# RNS.net
KiCad netlist of a schematic drawn in EAGLE
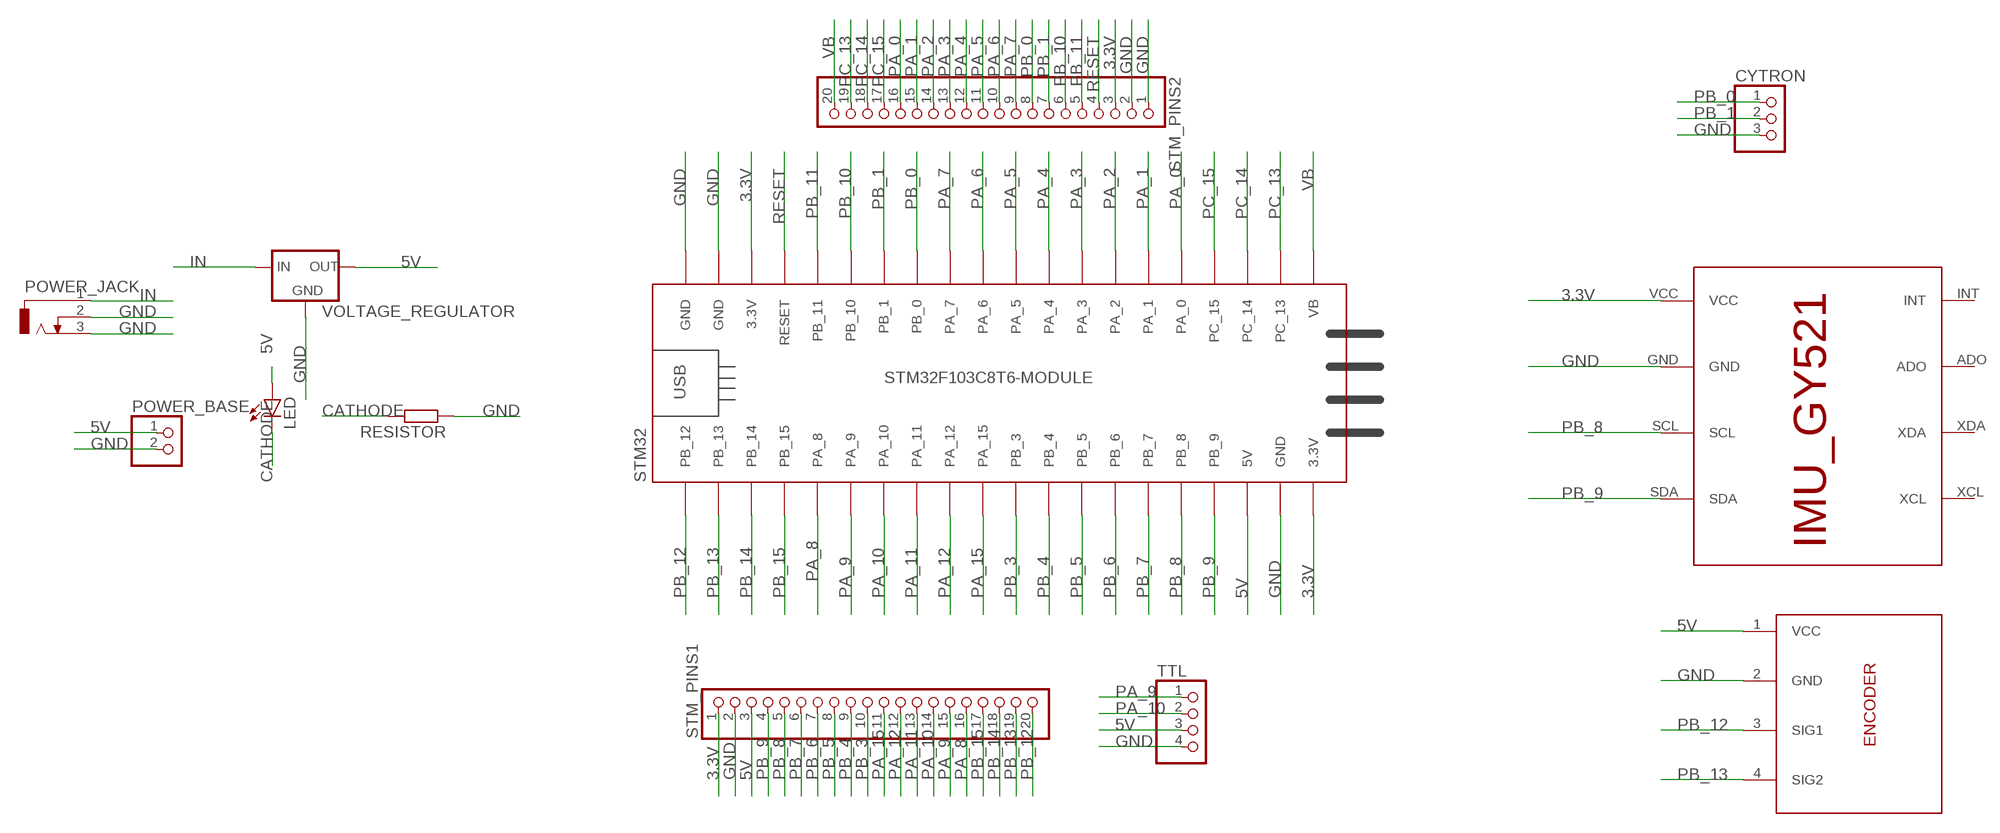
[diagram p0: schematic, sheet 1]

(export (version "E")
  (design (tool "Eeschema 10.0.6"))
  (components
    (comp (ref "CYTRON")
      (value "PINHD-3_DATA")
      (footprint "eagle-import:1X03_DATA")
      (libsource (lib "eagle-import") (part "PINHD-3_DATA"))
    )
    (comp (ref "ENCODER")
      (value "ENCODER")
      (footprint "eagle-import:1X04_DATA")
      (libsource (lib "eagle-import") (part "ENCODER"))
    )
    (comp (ref "IMU")
      (value "IMU_ROBOCON_GY521")
      (footprint "eagle-import:IMU_GY521")
      (libsource (lib "eagle-import") (part "IMU_ROBOCON_GY521"))
    )
    (comp (ref "LED")
      (value "LED5MM")
      (footprint "eagle-import:LED5MM")
      (libsource (lib "eagle-import") (part "LED5MM"))
    )
    (comp (ref "POWER_BASE")
      (value "PINHD-2_DATA")
      (footprint "eagle-import:1X02_DATA")
      (libsource (lib "eagle-import") (part "PINHD-2_DATA"))
    )
    (comp (ref "POWER_JACK")
      (value "CON_JACK")
      (footprint "eagle-import:DCJ0303")
      (libsource (lib "eagle-import") (part "CON_JACK"))
    )
    (comp (ref "RESISTOR")
      (value "R-EU_0207/12")
      (footprint "eagle-import:0207_12")
      (libsource (lib "eagle-import") (part "R-EU_0207/12"))
    )
    (comp (ref "STM32")
      (value "STM32F103C8T6-MODULE")
      (footprint "eagle-import:STM32F103C8T6-MODULE")
      (libsource (lib "eagle-import") (part "STM32F103C8T6-MODULE"))
    )
    (comp (ref "STM_PINS1")
      (value "PINHD-1X20")
      (footprint "eagle-import:1X20")
      (libsource (lib "eagle-import") (part "PINHD-1X20"))
    )
    (comp (ref "STM_PINS2")
      (value "PINHD-1X20")
      (footprint "eagle-import:1X20")
      (libsource (lib "eagle-import") (part "PINHD-1X20"))
    )
    (comp (ref "TTL")
      (value "PINHD-1X4")
      (footprint "eagle-import:1X04")
      (libsource (lib "eagle-import") (part "PINHD-1X4"))
    )
    (comp (ref "VOLTAGE_REGULATOR")
      (value "78XXS")
      (footprint "eagle-import:78XXS")
      (libsource (lib "eagle-import") (part "78XXS"))
    )
  )
  (nets
    (net (code "1") (name "/3.3V") (class "Default")
      (node (ref "IMU") (pin "VCC") (pinfunction "VCC_VCC") (pintype "bidirectional"))
      (node (ref "STM32") (pin "3.3V_1") (pinfunction "3.3V_3.3V_1") (pintype "bidirectional"))
      (node (ref "STM32") (pin "3.3V_2") (pinfunction "3.3V_3.3V_2") (pintype "bidirectional"))
      (node (ref "STM_PINS1") (pin "1") (pinfunction "1_1") (pintype "passive"))
      (node (ref "STM_PINS2") (pin "3") (pinfunction "3_3") (pintype "passive"))
    )
    (net (code "2") (name "/5V") (class "Default")
      (node (ref "ENCODER") (pin "1") (pinfunction "VCC_1") (pintype "bidirectional"))
      (node (ref "LED") (pin "A") (pinfunction "A_A") (pintype "passive"))
      (node (ref "POWER_BASE") (pin "1") (pinfunction "1_1") (pintype "passive"))
      (node (ref "STM32") (pin "5V") (pinfunction "5V_5V") (pintype "bidirectional"))
      (node (ref "STM_PINS1") (pin "3") (pinfunction "3_3") (pintype "passive"))
      (node (ref "TTL") (pin "3") (pinfunction "3_3") (pintype "passive"))
      (node (ref "VOLTAGE_REGULATOR") (pin "OUT") (pinfunction "OUT_OUT") (pintype "passive"))
    )
    (net (code "3") (name "/CATHODE") (class "Default")
      (node (ref "LED") (pin "K") (pinfunction "C_K") (pintype "passive"))
      (node (ref "RESISTOR") (pin "2") (pinfunction "2_2") (pintype "passive"))
    )
    (net (code "4") (name "/GND") (class "Default")
      (node (ref "CYTRON") (pin "3") (pinfunction "3_3") (pintype "passive"))
      (node (ref "ENCODER") (pin "2") (pinfunction "GND_2") (pintype "bidirectional"))
      (node (ref "IMU") (pin "GND") (pinfunction "GND_GND") (pintype "bidirectional"))
      (node (ref "POWER_BASE") (pin "2") (pinfunction "2_2") (pintype "passive"))
      (node (ref "POWER_JACK") (pin "2") (pinfunction "2_2") (pintype "passive"))
      (node (ref "POWER_JACK") (pin "3") (pinfunction "3_3") (pintype "passive"))
      (node (ref "RESISTOR") (pin "1") (pinfunction "1_1") (pintype "passive"))
      (node (ref "STM32") (pin "GND_1") (pinfunction "GND_GND_1") (pintype "bidirectional"))
      (node (ref "STM32") (pin "GND_2") (pinfunction "GND_GND_2") (pintype "bidirectional"))
      (node (ref "STM32") (pin "GND_3") (pinfunction "GND_GND_3") (pintype "power_in"))
      (node (ref "STM_PINS1") (pin "2") (pinfunction "2_2") (pintype "passive"))
      (node (ref "STM_PINS2") (pin "1") (pinfunction "1_1") (pintype "passive"))
      (node (ref "STM_PINS2") (pin "2") (pinfunction "2_2") (pintype "passive"))
      (node (ref "TTL") (pin "4") (pinfunction "4_4") (pintype "passive"))
      (node (ref "VOLTAGE_REGULATOR") (pin "GND") (pinfunction "GND_GND") (pintype "input"))
    )
    (net (code "5") (name "/IN") (class "Default")
      (node (ref "POWER_JACK") (pin "1") (pinfunction "1_1") (pintype "passive"))
      (node (ref "VOLTAGE_REGULATOR") (pin "IN") (pinfunction "IN_IN") (pintype "input"))
    )
    (net (code "6") (name "/PA_0") (class "Default")
      (node (ref "STM32") (pin "PA_0") (pinfunction "PA_0_PA_0") (pintype "bidirectional"))
      (node (ref "STM_PINS2") (pin "16") (pinfunction "16_16") (pintype "passive"))
    )
    (net (code "7") (name "/PA_1") (class "Default")
      (node (ref "STM32") (pin "PA_1") (pinfunction "PA_1_PA_1") (pintype "bidirectional"))
      (node (ref "STM_PINS2") (pin "15") (pinfunction "15_15") (pintype "passive"))
    )
    (net (code "8") (name "/PA_2") (class "Default")
      (node (ref "STM32") (pin "PA_2") (pinfunction "PA_2_PA_2") (pintype "bidirectional"))
      (node (ref "STM_PINS2") (pin "14") (pinfunction "14_14") (pintype "passive"))
    )
    (net (code "9") (name "/PA_3") (class "Default")
      (node (ref "STM32") (pin "PA_3") (pinfunction "PA_3_PA_3") (pintype "bidirectional"))
      (node (ref "STM_PINS2") (pin "13") (pinfunction "13_13") (pintype "passive"))
    )
    (net (code "10") (name "/PA_4") (class "Default")
      (node (ref "STM32") (pin "PA_4") (pinfunction "PA_4_PA_4") (pintype "bidirectional"))
      (node (ref "STM_PINS2") (pin "12") (pinfunction "12_12") (pintype "passive"))
    )
    (net (code "11") (name "/PA_5") (class "Default")
      (node (ref "STM32") (pin "PA_5") (pinfunction "PA_5_PA_5") (pintype "bidirectional"))
      (node (ref "STM_PINS2") (pin "11") (pinfunction "11_11") (pintype "passive"))
    )
    (net (code "12") (name "/PA_6") (class "Default")
      (node (ref "STM32") (pin "PA_6") (pinfunction "PA_6_PA_6") (pintype "bidirectional"))
      (node (ref "STM_PINS2") (pin "10") (pinfunction "10_10") (pintype "passive"))
    )
    (net (code "13") (name "/PA_7") (class "Default")
      (node (ref "STM32") (pin "PA_7") (pinfunction "PA_7_PA_7") (pintype "bidirectional"))
      (node (ref "STM_PINS2") (pin "9") (pinfunction "9_9") (pintype "passive"))
    )
    (net (code "14") (name "/PA_8") (class "Default")
      (node (ref "STM32") (pin "PA_8") (pinfunction "PA_8_PA_8") (pintype "bidirectional"))
      (node (ref "STM_PINS1") (pin "16") (pinfunction "16_16") (pintype "passive"))
    )
    (net (code "15") (name "/PA_9") (class "Default")
      (node (ref "STM32") (pin "PA_9") (pinfunction "PA_9_PA_9") (pintype "bidirectional"))
      (node (ref "STM_PINS1") (pin "15") (pinfunction "15_15") (pintype "passive"))
      (node (ref "TTL") (pin "1") (pinfunction "1_1") (pintype "passive"))
    )
    (net (code "16") (name "/PA_10") (class "Default")
      (node (ref "STM32") (pin "PA_10") (pinfunction "PA_10_PA_10") (pintype "bidirectional"))
      (node (ref "STM_PINS1") (pin "14") (pinfunction "14_14") (pintype "passive"))
      (node (ref "TTL") (pin "2") (pinfunction "2_2") (pintype "passive"))
    )
    (net (code "17") (name "/PA_11") (class "Default")
      (node (ref "STM32") (pin "PA_11") (pinfunction "PA_11_PA_11") (pintype "bidirectional"))
      (node (ref "STM_PINS1") (pin "13") (pinfunction "13_13") (pintype "passive"))
    )
    (net (code "18") (name "/PA_12") (class "Default")
      (node (ref "STM32") (pin "PA_12") (pinfunction "PA_12_PA_12") (pintype "bidirectional"))
      (node (ref "STM_PINS1") (pin "12") (pinfunction "12_12") (pintype "passive"))
    )
    (net (code "19") (name "/PA_15") (class "Default")
      (node (ref "STM32") (pin "PA_15") (pinfunction "PA_15_PA_15") (pintype "bidirectional"))
      (node (ref "STM_PINS1") (pin "11") (pinfunction "11_11") (pintype "passive"))
    )
    (net (code "20") (name "/PB_0") (class "Default")
      (node (ref "CYTRON") (pin "1") (pinfunction "1_1") (pintype "passive"))
      (node (ref "STM32") (pin "PB_0") (pinfunction "PB_0_PB_0") (pintype "bidirectional"))
      (node (ref "STM_PINS2") (pin "8") (pinfunction "8_8") (pintype "passive"))
    )
    (net (code "21") (name "/PB_1") (class "Default")
      (node (ref "CYTRON") (pin "2") (pinfunction "2_2") (pintype "passive"))
      (node (ref "STM32") (pin "PB_1") (pinfunction "PB_1_PB_1") (pintype "bidirectional"))
      (node (ref "STM_PINS2") (pin "7") (pinfunction "7_7") (pintype "passive"))
    )
    (net (code "22") (name "/PB_3") (class "Default")
      (node (ref "STM32") (pin "PB_3") (pinfunction "PB_3_PB_3") (pintype "bidirectional"))
      (node (ref "STM_PINS1") (pin "10") (pinfunction "10_10") (pintype "passive"))
    )
    (net (code "23") (name "/PB_4") (class "Default")
      (node (ref "STM32") (pin "PB_4") (pinfunction "PB_4_PB_4") (pintype "bidirectional"))
      (node (ref "STM_PINS1") (pin "9") (pinfunction "9_9") (pintype "passive"))
    )
    (net (code "24") (name "/PB_5") (class "Default")
      (node (ref "STM32") (pin "PB_5") (pinfunction "PB_5_PB_5") (pintype "bidirectional"))
      (node (ref "STM_PINS1") (pin "8") (pinfunction "8_8") (pintype "passive"))
    )
    (net (code "25") (name "/PB_6") (class "Default")
      (node (ref "STM32") (pin "PB_6") (pinfunction "PB_6_PB_6") (pintype "bidirectional"))
      (node (ref "STM_PINS1") (pin "7") (pinfunction "7_7") (pintype "passive"))
    )
    (net (code "26") (name "/PB_7") (class "Default")
      (node (ref "STM32") (pin "PB_7") (pinfunction "PB_7_PB_7") (pintype "bidirectional"))
      (node (ref "STM_PINS1") (pin "6") (pinfunction "6_6") (pintype "passive"))
    )
    (net (code "27") (name "/PB_8") (class "Default")
      (node (ref "IMU") (pin "SCL") (pinfunction "SCL_SCL") (pintype "bidirectional"))
      (node (ref "STM32") (pin "PB_8") (pinfunction "PB_8_PB_8") (pintype "bidirectional"))
      (node (ref "STM_PINS1") (pin "5") (pinfunction "5_5") (pintype "passive"))
    )
    (net (code "28") (name "/PB_9") (class "Default")
      (node (ref "IMU") (pin "SDA") (pinfunction "SDA_SDA") (pintype "bidirectional"))
      (node (ref "STM32") (pin "PB_9") (pinfunction "PB_9_PB_9") (pintype "bidirectional"))
      (node (ref "STM_PINS1") (pin "4") (pinfunction "4_4") (pintype "passive"))
    )
    (net (code "29") (name "/PB_10") (class "Default")
      (node (ref "STM32") (pin "PB_10") (pinfunction "PB_10_PB_10") (pintype "bidirectional"))
      (node (ref "STM_PINS2") (pin "6") (pinfunction "6_6") (pintype "passive"))
    )
    (net (code "30") (name "/PB_11") (class "Default")
      (node (ref "STM32") (pin "PB_11") (pinfunction "PB_11_PB_11") (pintype "bidirectional"))
      (node (ref "STM_PINS2") (pin "5") (pinfunction "5_5") (pintype "passive"))
    )
    (net (code "31") (name "/PB_12") (class "Default")
      (node (ref "ENCODER") (pin "3") (pinfunction "SIG1_3") (pintype "bidirectional"))
      (node (ref "STM32") (pin "PB_12") (pinfunction "PB_12_PB_12") (pintype "bidirectional"))
      (node (ref "STM_PINS1") (pin "20") (pinfunction "20_20") (pintype "passive"))
    )
    (net (code "32") (name "/PB_13") (class "Default")
      (node (ref "ENCODER") (pin "4") (pinfunction "SIG2_4") (pintype "bidirectional"))
      (node (ref "STM32") (pin "PB_13") (pinfunction "PB_13_PB_13") (pintype "bidirectional"))
      (node (ref "STM_PINS1") (pin "19") (pinfunction "19_19") (pintype "passive"))
    )
    (net (code "33") (name "/PB_14") (class "Default")
      (node (ref "STM32") (pin "PB_14") (pinfunction "PB_14_PB_14") (pintype "bidirectional"))
      (node (ref "STM_PINS1") (pin "18") (pinfunction "18_18") (pintype "passive"))
    )
    (net (code "34") (name "/PB_15") (class "Default")
      (node (ref "STM32") (pin "PB_15") (pinfunction "PB_15_PB_15") (pintype "bidirectional"))
      (node (ref "STM_PINS1") (pin "17") (pinfunction "17_17") (pintype "passive"))
    )
    (net (code "35") (name "/PC_13") (class "Default")
      (node (ref "STM32") (pin "PC_13") (pinfunction "PC_13_PC_13") (pintype "bidirectional"))
      (node (ref "STM_PINS2") (pin "19") (pinfunction "19_19") (pintype "passive"))
    )
    (net (code "36") (name "/PC_14") (class "Default")
      (node (ref "STM32") (pin "PC_14") (pinfunction "PC_14_PC_14") (pintype "bidirectional"))
      (node (ref "STM_PINS2") (pin "18") (pinfunction "18_18") (pintype "passive"))
    )
    (net (code "37") (name "/PC_15") (class "Default")
      (node (ref "STM32") (pin "PC_15") (pinfunction "PC_15_PC_15") (pintype "bidirectional"))
      (node (ref "STM_PINS2") (pin "17") (pinfunction "17_17") (pintype "passive"))
    )
    (net (code "38") (name "/RESET") (class "Default")
      (node (ref "STM32") (pin "RESET") (pinfunction "RESET_RESET") (pintype "bidirectional"))
      (node (ref "STM_PINS2") (pin "4") (pinfunction "4_4") (pintype "passive"))
    )
    (net (code "39") (name "/VB") (class "Default")
      (node (ref "STM32") (pin "VB") (pinfunction "VB_VB") (pintype "bidirectional"))
      (node (ref "STM_PINS2") (pin "20") (pinfunction "20_20") (pintype "passive"))
    )
    (net (code "40") (name "unconnected-(IMU-PadADO)") (class "Default")
      (node (ref "IMU") (pin "ADO") (pinfunction "ADO_ADO") (pintype "bidirectional"))
    )
    (net (code "41") (name "unconnected-(IMU-PadINT)") (class "Default")
      (node (ref "IMU") (pin "INT") (pinfunction "INT_INT") (pintype "bidirectional"))
    )
    (net (code "42") (name "unconnected-(IMU-PadXCL)") (class "Default")
      (node (ref "IMU") (pin "XCL") (pinfunction "XCL_XCL") (pintype "bidirectional"))
    )
    (net (code "43") (name "unconnected-(IMU-PadXDA)") (class "Default")
      (node (ref "IMU") (pin "XDA") (pinfunction "XDA_XDA") (pintype "bidirectional"))
    )
  )
)
